# 2_cyber60-smk_matrix.net
KiCad netlist of a schematic drawn in Altium Designer
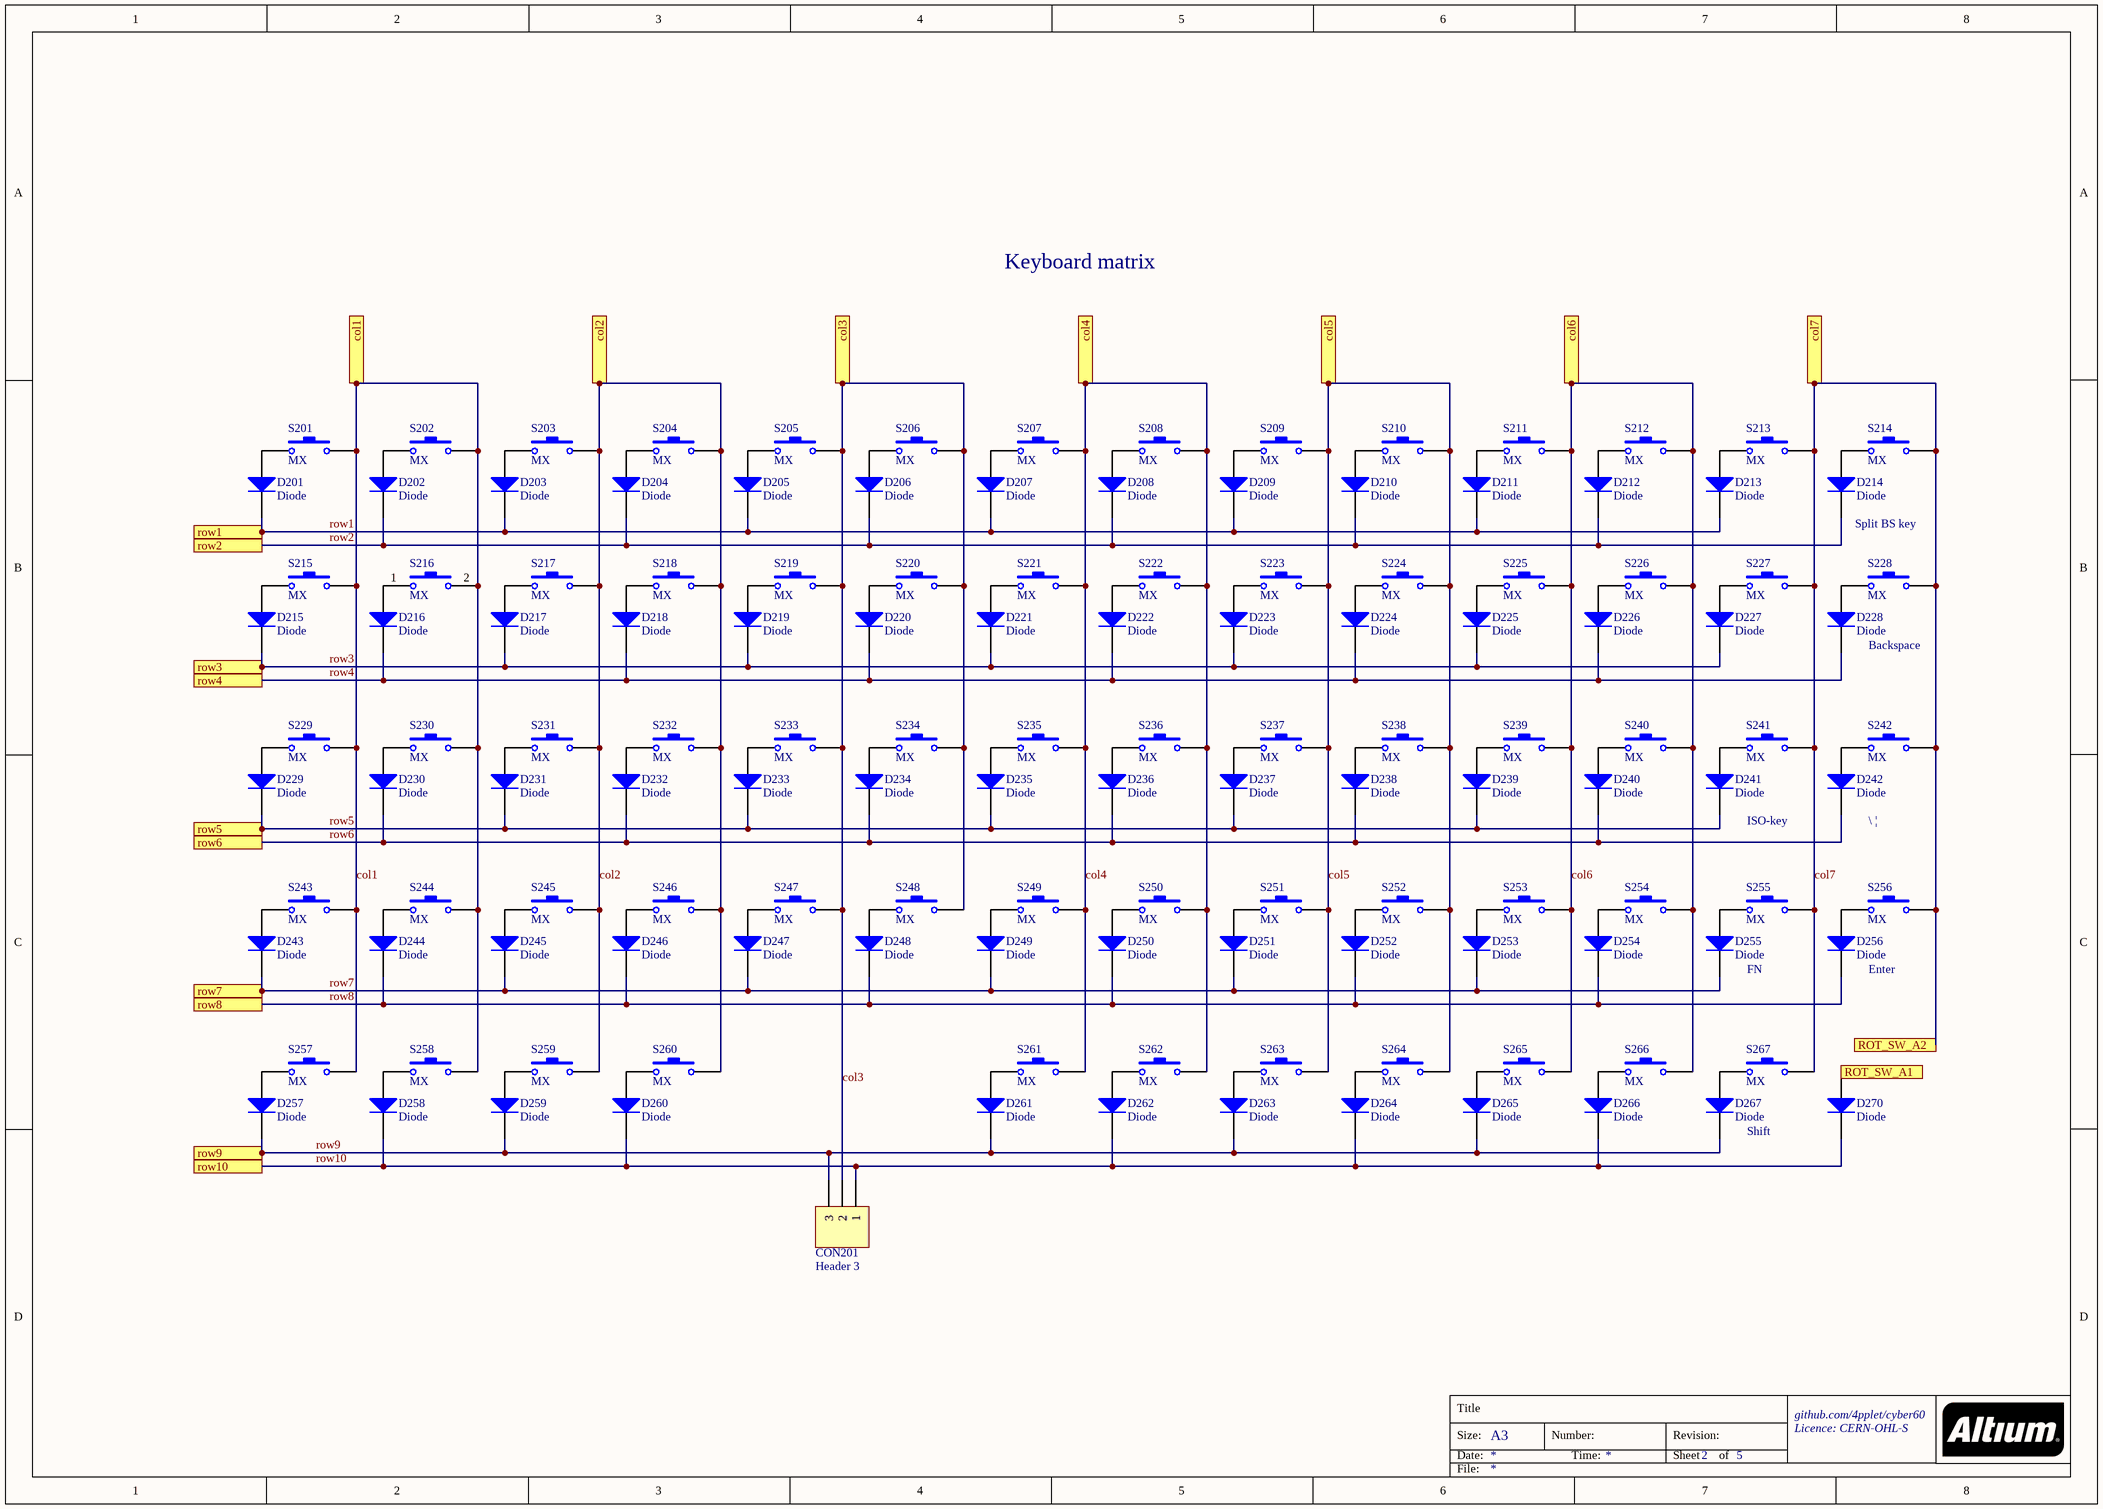
[diagram p0: 2_cyber60-smk_matrix.SchDoc]

(export (version "E")
  (design (tool "Eeschema 10.0.6"))
  (components
    (comp (ref "CON201")
      (value "Header 3")
      (footprint "HDR1X3")
      (description "Header, 3-Pin")
      (libsource (lib "Miscellaneous Connectors") (part "Header 3"))
    )
    (comp (ref "D201")
      (value "Diode")
      (footprint "SOD-123")
      (description "Default Diode")
      (fields (field (name "LCSC PART #") "C81598") (field (name "MRF.PART") "1N4148W"))
      (libsource (lib "Miscellaneous Devices") (part "Diode"))
    )
    (comp (ref "D202")
      (value "Diode")
      (footprint "SOD-123")
      (description "Default Diode")
      (fields (field (name "LCSC PART #") "C81598") (field (name "MRF.PART") "1N4148W"))
      (libsource (lib "Miscellaneous Devices") (part "Diode"))
    )
    (comp (ref "D203")
      (value "Diode")
      (footprint "SOD-123")
      (description "Default Diode")
      (fields (field (name "LCSC PART #") "C81598") (field (name "MRF.PART") "1N4148W"))
      (libsource (lib "Miscellaneous Devices") (part "Diode"))
    )
    (comp (ref "D204")
      (value "Diode")
      (footprint "SOD-123")
      (description "Default Diode")
      (fields (field (name "LCSC PART #") "C81598") (field (name "MRF.PART") "1N4148W"))
      (libsource (lib "Miscellaneous Devices") (part "Diode"))
    )
    (comp (ref "D205")
      (value "Diode")
      (footprint "SOD-123")
      (description "Default Diode")
      (fields (field (name "LCSC PART #") "C81598") (field (name "MRF.PART") "1N4148W"))
      (libsource (lib "Miscellaneous Devices") (part "Diode"))
    )
    (comp (ref "D206")
      (value "Diode")
      (footprint "SOD-123")
      (description "Default Diode")
      (fields (field (name "LCSC PART #") "C81598") (field (name "MRF.PART") "1N4148W"))
      (libsource (lib "Miscellaneous Devices") (part "Diode"))
    )
    (comp (ref "D207")
      (value "Diode")
      (footprint "SOD-123")
      (description "Default Diode")
      (fields (field (name "LCSC PART #") "C81598") (field (name "MRF.PART") "1N4148W"))
      (libsource (lib "Miscellaneous Devices") (part "Diode"))
    )
    (comp (ref "D208")
      (value "Diode")
      (footprint "SOD-123")
      (description "Default Diode")
      (fields (field (name "LCSC PART #") "C81598") (field (name "MRF.PART") "1N4148W"))
      (libsource (lib "Miscellaneous Devices") (part "Diode"))
    )
    (comp (ref "D209")
      (value "Diode")
      (footprint "SOD-123")
      (description "Default Diode")
      (fields (field (name "LCSC PART #") "C81598") (field (name "MRF.PART") "1N4148W"))
      (libsource (lib "Miscellaneous Devices") (part "Diode"))
    )
    (comp (ref "D210")
      (value "Diode")
      (footprint "SOD-123")
      (description "Default Diode")
      (fields (field (name "LCSC PART #") "C81598") (field (name "MRF.PART") "1N4148W"))
      (libsource (lib "Miscellaneous Devices") (part "Diode"))
    )
    (comp (ref "D211")
      (value "Diode")
      (footprint "SOD-123")
      (description "Default Diode")
      (fields (field (name "LCSC PART #") "C81598") (field (name "MRF.PART") "1N4148W"))
      (libsource (lib "Miscellaneous Devices") (part "Diode"))
    )
    (comp (ref "D212")
      (value "Diode")
      (footprint "SOD-123")
      (description "Default Diode")
      (fields (field (name "LCSC PART #") "C81598") (field (name "MRF.PART") "1N4148W"))
      (libsource (lib "Miscellaneous Devices") (part "Diode"))
    )
    (comp (ref "D213")
      (value "Diode")
      (footprint "SOD-123")
      (description "Default Diode")
      (fields (field (name "LCSC PART #") "C81598") (field (name "MRF.PART") "1N4148W"))
      (libsource (lib "Miscellaneous Devices") (part "Diode"))
    )
    (comp (ref "D214")
      (value "Diode")
      (footprint "SOD-123")
      (description "Default Diode")
      (fields (field (name "LCSC PART #") "C81598") (field (name "MRF.PART") "1N4148W"))
      (libsource (lib "Miscellaneous Devices") (part "Diode"))
    )
    (comp (ref "D215")
      (value "Diode")
      (footprint "SOD-123")
      (description "Default Diode")
      (fields (field (name "LCSC PART #") "C81598") (field (name "MRF.PART") "1N4148W"))
      (libsource (lib "Miscellaneous Devices") (part "Diode"))
    )
    (comp (ref "D216")
      (value "Diode")
      (footprint "SOD-123")
      (description "Default Diode")
      (fields (field (name "LCSC PART #") "C81598") (field (name "MRF.PART") "1N4148W"))
      (libsource (lib "Miscellaneous Devices") (part "Diode"))
    )
    (comp (ref "D217")
      (value "Diode")
      (footprint "SOD-123")
      (description "Default Diode")
      (fields (field (name "LCSC PART #") "C81598") (field (name "MRF.PART") "1N4148W"))
      (libsource (lib "Miscellaneous Devices") (part "Diode"))
    )
    (comp (ref "D218")
      (value "Diode")
      (footprint "SOD-123")
      (description "Default Diode")
      (fields (field (name "LCSC PART #") "C81598") (field (name "MRF.PART") "1N4148W"))
      (libsource (lib "Miscellaneous Devices") (part "Diode"))
    )
    (comp (ref "D219")
      (value "Diode")
      (footprint "SOD-123")
      (description "Default Diode")
      (fields (field (name "LCSC PART #") "C81598") (field (name "MRF.PART") "1N4148W"))
      (libsource (lib "Miscellaneous Devices") (part "Diode"))
    )
    (comp (ref "D220")
      (value "Diode")
      (footprint "SOD-123")
      (description "Default Diode")
      (fields (field (name "LCSC PART #") "C81598") (field (name "MRF.PART") "1N4148W"))
      (libsource (lib "Miscellaneous Devices") (part "Diode"))
    )
    (comp (ref "D221")
      (value "Diode")
      (footprint "SOD-123")
      (description "Default Diode")
      (fields (field (name "LCSC PART #") "C81598") (field (name "MRF.PART") "1N4148W"))
      (libsource (lib "Miscellaneous Devices") (part "Diode"))
    )
    (comp (ref "D222")
      (value "Diode")
      (footprint "SOD-123")
      (description "Default Diode")
      (fields (field (name "LCSC PART #") "C81598") (field (name "MRF.PART") "1N4148W"))
      (libsource (lib "Miscellaneous Devices") (part "Diode"))
    )
    (comp (ref "D223")
      (value "Diode")
      (footprint "SOD-123")
      (description "Default Diode")
      (fields (field (name "LCSC PART #") "C81598") (field (name "MRF.PART") "1N4148W"))
      (libsource (lib "Miscellaneous Devices") (part "Diode"))
    )
    (comp (ref "D224")
      (value "Diode")
      (footprint "SOD-123")
      (description "Default Diode")
      (fields (field (name "LCSC PART #") "C81598") (field (name "MRF.PART") "1N4148W"))
      (libsource (lib "Miscellaneous Devices") (part "Diode"))
    )
    (comp (ref "D225")
      (value "Diode")
      (footprint "SOD-123")
      (description "Default Diode")
      (fields (field (name "LCSC PART #") "C81598") (field (name "MRF.PART") "1N4148W"))
      (libsource (lib "Miscellaneous Devices") (part "Diode"))
    )
    (comp (ref "D226")
      (value "Diode")
      (footprint "SOD-123")
      (description "Default Diode")
      (fields (field (name "LCSC PART #") "C81598") (field (name "MRF.PART") "1N4148W"))
      (libsource (lib "Miscellaneous Devices") (part "Diode"))
    )
    (comp (ref "D227")
      (value "Diode")
      (footprint "SOD-123")
      (description "Default Diode")
      (fields (field (name "LCSC PART #") "C81598") (field (name "MRF.PART") "1N4148W"))
      (libsource (lib "Miscellaneous Devices") (part "Diode"))
    )
    (comp (ref "D228")
      (value "Diode")
      (footprint "SOD-123")
      (description "Default Diode")
      (fields (field (name "LCSC PART #") "C81598") (field (name "MRF.PART") "1N4148W"))
      (libsource (lib "Miscellaneous Devices") (part "Diode"))
    )
    (comp (ref "D229")
      (value "Diode")
      (footprint "SOD-123")
      (description "Default Diode")
      (fields (field (name "LCSC PART #") "C81598") (field (name "MRF.PART") "1N4148W"))
      (libsource (lib "Miscellaneous Devices") (part "Diode"))
    )
    (comp (ref "D230")
      (value "Diode")
      (footprint "SOD-123")
      (description "Default Diode")
      (fields (field (name "LCSC PART #") "C81598") (field (name "MRF.PART") "1N4148W"))
      (libsource (lib "Miscellaneous Devices") (part "Diode"))
    )
    (comp (ref "D231")
      (value "Diode")
      (footprint "SOD-123")
      (description "Default Diode")
      (fields (field (name "LCSC PART #") "C81598") (field (name "MRF.PART") "1N4148W"))
      (libsource (lib "Miscellaneous Devices") (part "Diode"))
    )
    (comp (ref "D232")
      (value "Diode")
      (footprint "SOD-123")
      (description "Default Diode")
      (fields (field (name "LCSC PART #") "C81598") (field (name "MRF.PART") "1N4148W"))
      (libsource (lib "Miscellaneous Devices") (part "Diode"))
    )
    (comp (ref "D233")
      (value "Diode")
      (footprint "SOD-123")
      (description "Default Diode")
      (fields (field (name "LCSC PART #") "C81598") (field (name "MRF.PART") "1N4148W"))
      (libsource (lib "Miscellaneous Devices") (part "Diode"))
    )
    (comp (ref "D234")
      (value "Diode")
      (footprint "SOD-123")
      (description "Default Diode")
      (fields (field (name "LCSC PART #") "C81598") (field (name "MRF.PART") "1N4148W"))
      (libsource (lib "Miscellaneous Devices") (part "Diode"))
    )
    (comp (ref "D235")
      (value "Diode")
      (footprint "SOD-123")
      (description "Default Diode")
      (fields (field (name "LCSC PART #") "C81598") (field (name "MRF.PART") "1N4148W"))
      (libsource (lib "Miscellaneous Devices") (part "Diode"))
    )
    (comp (ref "D236")
      (value "Diode")
      (footprint "SOD-123")
      (description "Default Diode")
      (fields (field (name "LCSC PART #") "C81598") (field (name "MRF.PART") "1N4148W"))
      (libsource (lib "Miscellaneous Devices") (part "Diode"))
    )
    (comp (ref "D237")
      (value "Diode")
      (footprint "SOD-123")
      (description "Default Diode")
      (fields (field (name "LCSC PART #") "C81598") (field (name "MRF.PART") "1N4148W"))
      (libsource (lib "Miscellaneous Devices") (part "Diode"))
    )
    (comp (ref "D238")
      (value "Diode")
      (footprint "SOD-123")
      (description "Default Diode")
      (fields (field (name "LCSC PART #") "C81598") (field (name "MRF.PART") "1N4148W"))
      (libsource (lib "Miscellaneous Devices") (part "Diode"))
    )
    (comp (ref "D239")
      (value "Diode")
      (footprint "SOD-123")
      (description "Default Diode")
      (fields (field (name "LCSC PART #") "C81598") (field (name "MRF.PART") "1N4148W"))
      (libsource (lib "Miscellaneous Devices") (part "Diode"))
    )
    (comp (ref "D240")
      (value "Diode")
      (footprint "SOD-123")
      (description "Default Diode")
      (fields (field (name "LCSC PART #") "C81598") (field (name "MRF.PART") "1N4148W"))
      (libsource (lib "Miscellaneous Devices") (part "Diode"))
    )
    (comp (ref "D241")
      (value "Diode")
      (footprint "SOD-123")
      (description "Default Diode")
      (fields (field (name "LCSC PART #") "C81598") (field (name "MRF.PART") "1N4148W"))
      (libsource (lib "Miscellaneous Devices") (part "Diode"))
    )
    (comp (ref "D242")
      (value "Diode")
      (footprint "SOD-123")
      (description "Default Diode")
      (fields (field (name "LCSC PART #") "C81598") (field (name "MRF.PART") "1N4148W"))
      (libsource (lib "Miscellaneous Devices") (part "Diode"))
    )
    (comp (ref "D243")
      (value "Diode")
      (footprint "SOD-123")
      (description "Default Diode")
      (fields (field (name "LCSC PART #") "C81598") (field (name "MRF.PART") "1N4148W"))
      (libsource (lib "Miscellaneous Devices") (part "Diode"))
    )
    (comp (ref "D244")
      (value "Diode")
      (footprint "SOD-123")
      (description "Default Diode")
      (fields (field (name "LCSC PART #") "C81598") (field (name "MRF.PART") "1N4148W"))
      (libsource (lib "Miscellaneous Devices") (part "Diode"))
    )
    (comp (ref "D245")
      (value "Diode")
      (footprint "SOD-123")
      (description "Default Diode")
      (fields (field (name "LCSC PART #") "C81598") (field (name "MRF.PART") "1N4148W"))
      (libsource (lib "Miscellaneous Devices") (part "Diode"))
    )
    (comp (ref "D246")
      (value "Diode")
      (footprint "SOD-123")
      (description "Default Diode")
      (fields (field (name "LCSC PART #") "C81598") (field (name "MRF.PART") "1N4148W"))
      (libsource (lib "Miscellaneous Devices") (part "Diode"))
    )
    (comp (ref "D247")
      (value "Diode")
      (footprint "SOD-123")
      (description "Default Diode")
      (fields (field (name "LCSC PART #") "C81598") (field (name "MRF.PART") "1N4148W"))
      (libsource (lib "Miscellaneous Devices") (part "Diode"))
    )
    (comp (ref "D248")
      (value "Diode")
      (footprint "SOD-123")
      (description "Default Diode")
      (fields (field (name "LCSC PART #") "C81598") (field (name "MRF.PART") "1N4148W"))
      (libsource (lib "Miscellaneous Devices") (part "Diode"))
    )
    (comp (ref "D249")
      (value "Diode")
      (footprint "SOD-123")
      (description "Default Diode")
      (fields (field (name "LCSC PART #") "C81598") (field (name "MRF.PART") "1N4148W"))
      (libsource (lib "Miscellaneous Devices") (part "Diode"))
    )
    (comp (ref "D250")
      (value "Diode")
      (footprint "SOD-123")
      (description "Default Diode")
      (fields (field (name "LCSC PART #") "C81598") (field (name "MRF.PART") "1N4148W"))
      (libsource (lib "Miscellaneous Devices") (part "Diode"))
    )
    (comp (ref "D251")
      (value "Diode")
      (footprint "SOD-123")
      (description "Default Diode")
      (fields (field (name "LCSC PART #") "C81598") (field (name "MRF.PART") "1N4148W"))
      (libsource (lib "Miscellaneous Devices") (part "Diode"))
    )
    (comp (ref "D252")
      (value "Diode")
      (footprint "SOD-123")
      (description "Default Diode")
      (fields (field (name "LCSC PART #") "C81598") (field (name "MRF.PART") "1N4148W"))
      (libsource (lib "Miscellaneous Devices") (part "Diode"))
    )
    (comp (ref "D253")
      (value "Diode")
      (footprint "SOD-123")
      (description "Default Diode")
      (fields (field (name "LCSC PART #") "C81598") (field (name "MRF.PART") "1N4148W"))
      (libsource (lib "Miscellaneous Devices") (part "Diode"))
    )
    (comp (ref "D254")
      (value "Diode")
      (footprint "SOD-123")
      (description "Default Diode")
      (fields (field (name "LCSC PART #") "C81598") (field (name "MRF.PART") "1N4148W"))
      (libsource (lib "Miscellaneous Devices") (part "Diode"))
    )
    (comp (ref "D255")
      (value "Diode")
      (footprint "SOD-123")
      (description "Default Diode")
      (fields (field (name "LCSC PART #") "C81598") (field (name "MRF.PART") "1N4148W"))
      (libsource (lib "Miscellaneous Devices") (part "Diode"))
    )
    (comp (ref "D256")
      (value "Diode")
      (footprint "SOD-123")
      (description "Default Diode")
      (fields (field (name "LCSC PART #") "C81598") (field (name "MRF.PART") "1N4148W"))
      (libsource (lib "Miscellaneous Devices") (part "Diode"))
    )
    (comp (ref "D257")
      (value "Diode")
      (footprint "SOD-123")
      (description "Default Diode")
      (fields (field (name "LCSC PART #") "C81598") (field (name "MRF.PART") "1N4148W"))
      (libsource (lib "Miscellaneous Devices") (part "Diode"))
    )
    (comp (ref "D258")
      (value "Diode")
      (footprint "SOD-123")
      (description "Default Diode")
      (fields (field (name "LCSC PART #") "C81598") (field (name "MRF.PART") "1N4148W"))
      (libsource (lib "Miscellaneous Devices") (part "Diode"))
    )
    (comp (ref "D259")
      (value "Diode")
      (footprint "SOD-123")
      (description "Default Diode")
      (fields (field (name "LCSC PART #") "C81598") (field (name "MRF.PART") "1N4148W"))
      (libsource (lib "Miscellaneous Devices") (part "Diode"))
    )
    (comp (ref "D260")
      (value "Diode")
      (footprint "SOD-123")
      (description "Default Diode")
      (fields (field (name "LCSC PART #") "C81598") (field (name "MRF.PART") "1N4148W"))
      (libsource (lib "Miscellaneous Devices") (part "Diode"))
    )
    (comp (ref "D261")
      (value "Diode")
      (footprint "SOD-123")
      (description "Default Diode")
      (fields (field (name "LCSC PART #") "C81598") (field (name "MRF.PART") "1N4148W"))
      (libsource (lib "Miscellaneous Devices") (part "Diode"))
    )
    (comp (ref "D262")
      (value "Diode")
      (footprint "SOD-123")
      (description "Default Diode")
      (fields (field (name "LCSC PART #") "C81598") (field (name "MRF.PART") "1N4148W"))
      (libsource (lib "Miscellaneous Devices") (part "Diode"))
    )
    (comp (ref "D263")
      (value "Diode")
      (footprint "SOD-123")
      (description "Default Diode")
      (fields (field (name "LCSC PART #") "C81598") (field (name "MRF.PART") "1N4148W"))
      (libsource (lib "Miscellaneous Devices") (part "Diode"))
    )
    (comp (ref "D264")
      (value "Diode")
      (footprint "SOD-123")
      (description "Default Diode")
      (fields (field (name "LCSC PART #") "C81598") (field (name "MRF.PART") "1N4148W"))
      (libsource (lib "Miscellaneous Devices") (part "Diode"))
    )
    (comp (ref "D265")
      (value "Diode")
      (footprint "SOD-123")
      (description "Default Diode")
      (fields (field (name "LCSC PART #") "C81598") (field (name "MRF.PART") "1N4148W"))
      (libsource (lib "Miscellaneous Devices") (part "Diode"))
    )
    (comp (ref "D266")
      (value "Diode")
      (footprint "SOD-123")
      (description "Default Diode")
      (fields (field (name "LCSC PART #") "C81598") (field (name "MRF.PART") "1N4148W"))
      (libsource (lib "Miscellaneous Devices") (part "Diode"))
    )
    (comp (ref "D267")
      (value "Diode")
      (footprint "SOD-123")
      (description "Default Diode")
      (fields (field (name "LCSC PART #") "C81598") (field (name "MRF.PART") "1N4148W"))
      (libsource (lib "Miscellaneous Devices") (part "Diode"))
    )
    (comp (ref "D270")
      (value "Diode")
      (footprint "SOD-123")
      (description "Default Diode")
      (fields (field (name "LCSC PART #") "C81598") (field (name "MRF.PART") "1N4148W"))
      (libsource (lib "Miscellaneous Devices") (part "Diode"))
    )
    (comp (ref "S201")
      (value "MX")
      (footprint "SMK-switch - switched polarity")
      (description "Switch")
      (libsource (lib "Miscellaneous Devices") (part "SW-PB"))
    )
    (comp (ref "S202")
      (value "MX")
      (footprint "SMK-switch - switched polarity")
      (description "Switch")
      (libsource (lib "Miscellaneous Devices") (part "SW-PB"))
    )
    (comp (ref "S203")
      (value "MX")
      (footprint "SMK-switch - switched polarity")
      (description "Switch")
      (libsource (lib "Miscellaneous Devices") (part "SW-PB"))
    )
    (comp (ref "S204")
      (value "MX")
      (footprint "SMK-switch")
      (description "Switch")
      (libsource (lib "Miscellaneous Devices") (part "SW-PB"))
    )
    (comp (ref "S205")
      (value "MX")
      (footprint "SMK-switch - switched polarity")
      (description "Switch")
      (libsource (lib "Miscellaneous Devices") (part "SW-PB"))
    )
    (comp (ref "S206")
      (value "MX")
      (footprint "SMK-switch - switched polarity")
      (description "Switch")
      (libsource (lib "Miscellaneous Devices") (part "SW-PB"))
    )
    (comp (ref "S207")
      (value "MX")
      (footprint "SMK-switch - switched polarity")
      (description "Switch")
      (libsource (lib "Miscellaneous Devices") (part "SW-PB"))
    )
    (comp (ref "S208")
      (value "MX")
      (footprint "SMK-switch - switched polarity")
      (description "Switch")
      (libsource (lib "Miscellaneous Devices") (part "SW-PB"))
    )
    (comp (ref "S209")
      (value "MX")
      (footprint "SMK-switch - switched polarity")
      (description "Switch")
      (libsource (lib "Miscellaneous Devices") (part "SW-PB"))
    )
    (comp (ref "S210")
      (value "MX")
      (footprint "SMK-switch - switched polarity")
      (description "Switch")
      (libsource (lib "Miscellaneous Devices") (part "SW-PB"))
    )
    (comp (ref "S211")
      (value "MX")
      (footprint "SMK-switch")
      (description "Switch")
      (libsource (lib "Miscellaneous Devices") (part "SW-PB"))
    )
    (comp (ref "S212")
      (value "MX")
      (footprint "SMK-switch - switched polarity")
      (description "Switch")
      (libsource (lib "Miscellaneous Devices") (part "SW-PB"))
    )
    (comp (ref "S213")
      (value "MX")
      (footprint "SMK-switch")
      (description "Switch")
      (libsource (lib "Miscellaneous Devices") (part "SW-PB"))
    )
    (comp (ref "S214")
      (value "MX")
      (footprint "SMK-switch")
      (description "Switch")
      (libsource (lib "Miscellaneous Devices") (part "SW-PB"))
    )
    (comp (ref "S215")
      (value "MX")
      (footprint "SMK-switch - 1.5U")
      (description "TAB")
      (libsource (lib "Miscellaneous Devices") (part "SW-PB"))
    )
    (comp (ref "S216")
      (value "MX")
      (footprint "SMK-switch - switched polarity")
      (description "Switch")
      (libsource (lib "") (part "SW-PB_1"))
    )
    (comp (ref "S217")
      (value "MX")
      (footprint "SMK-switch - switched polarity")
      (description "Switch")
      (libsource (lib "Miscellaneous Devices") (part "SW-PB"))
    )
    (comp (ref "S218")
      (value "MX")
      (footprint "SMK-switch - switched polarity")
      (description "Switch")
      (libsource (lib "Miscellaneous Devices") (part "SW-PB"))
    )
    (comp (ref "S219")
      (value "MX")
      (footprint "SMK-switch - switched polarity")
      (description "Switch")
      (libsource (lib "Miscellaneous Devices") (part "SW-PB"))
    )
    (comp (ref "S220")
      (value "MX")
      (footprint "SMK-switch")
      (description "Switch")
      (libsource (lib "Miscellaneous Devices") (part "SW-PB"))
    )
    (comp (ref "S221")
      (value "MX")
      (footprint "SMK-switch - switched polarity")
      (description "Switch")
      (libsource (lib "Miscellaneous Devices") (part "SW-PB"))
    )
    (comp (ref "S222")
      (value "MX")
      (footprint "SMK-switch - switched polarity")
      (description "Switch")
      (libsource (lib "Miscellaneous Devices") (part "SW-PB"))
    )
    (comp (ref "S223")
      (value "MX")
      (footprint "SMK-switch - switched polarity")
      (description "Switch")
      (libsource (lib "Miscellaneous Devices") (part "SW-PB"))
    )
    (comp (ref "S224")
      (value "MX")
      (footprint "SMK-switch - switched polarity")
      (description "Switch")
      (libsource (lib "Miscellaneous Devices") (part "SW-PB"))
    )
    (comp (ref "S225")
      (value "MX")
      (footprint "SMK-switch - switched polarity")
      (description "Switch")
      (libsource (lib "Miscellaneous Devices") (part "SW-PB"))
    )
    (comp (ref "S226")
      (value "MX")
      (footprint "SMK-switch")
      (description "Switch")
      (libsource (lib "Miscellaneous Devices") (part "SW-PB"))
    )
    (comp (ref "S227")
      (value "MX")
      (footprint "SMK-switch")
      (description "Switch")
      (libsource (lib "Miscellaneous Devices") (part "SW-PB"))
    )
    (comp (ref "S228")
      (value "MX")
      (footprint "SMK-switch - backspace")
      (description "Switch")
      (libsource (lib "Miscellaneous Devices") (part "SW-PB"))
    )
    (comp (ref "S229")
      (value "MX")
      (footprint "SMK-switch - CAPS")
      (description "Switch")
      (libsource (lib "Miscellaneous Devices") (part "SW-PB"))
    )
    (comp (ref "S230")
      (value "MX")
      (footprint "SMK-switch - switched polarity")
      (description "Switch")
      (libsource (lib "Miscellaneous Devices") (part "SW-PB"))
    )
    (comp (ref "S231")
      (value "MX")
      (footprint "SMK-switch - switched polarity")
      (description "Switch")
      (libsource (lib "Miscellaneous Devices") (part "SW-PB"))
    )
    (comp (ref "S232")
      (value "MX")
      (footprint "SMK-switch - switched polarity")
      (description "Switch")
      (libsource (lib "Miscellaneous Devices") (part "SW-PB"))
    )
    (comp (ref "S233")
      (value "MX")
      (footprint "SMK-switch - switched polarity")
      (description "Switch")
      (libsource (lib "Miscellaneous Devices") (part "SW-PB"))
    )
    (comp (ref "S234")
      (value "MX")
      (footprint "SMK-switch")
      (description "Switch")
      (libsource (lib "Miscellaneous Devices") (part "SW-PB"))
    )
    (comp (ref "S235")
      (value "MX")
      (footprint "SMK-switch - switched polarity")
      (description "Switch")
      (libsource (lib "Miscellaneous Devices") (part "SW-PB"))
    )
    (comp (ref "S236")
      (value "MX")
      (footprint "SMK-switch - switched polarity")
      (description "Switch")
      (libsource (lib "Miscellaneous Devices") (part "SW-PB"))
    )
    (comp (ref "S237")
      (value "MX")
      (footprint "SMK-switch - switched polarity")
      (description "Switch")
      (libsource (lib "Miscellaneous Devices") (part "SW-PB"))
    )
    (comp (ref "S238")
      (value "MX")
      (footprint "SMK-switch - switched polarity")
      (description "Switch")
      (libsource (lib "Miscellaneous Devices") (part "SW-PB"))
    )
    (comp (ref "S239")
      (value "MX")
      (footprint "SMK-switch")
      (description "Switch")
      (libsource (lib "Miscellaneous Devices") (part "SW-PB"))
    )
    (comp (ref "S240")
      (value "MX")
      (footprint "SMK-switch - switched polarity")
      (description "Switch")
      (libsource (lib "Miscellaneous Devices") (part "SW-PB"))
    )
    (comp (ref "S241")
      (value "MX")
      (footprint "SMK-switch")
      (description "Switch")
      (libsource (lib "Miscellaneous Devices") (part "SW-PB"))
    )
    (comp (ref "S242")
      (value "MX")
      (footprint "SMK-switch - 1.5U")
      (description "Switch")
      (libsource (lib "Miscellaneous Devices") (part "SW-PB"))
    )
    (comp (ref "S243")
      (value "MX")
      (footprint "SMK-switch - Left shift v2")
      (description "Switch")
      (libsource (lib "Miscellaneous Devices") (part "SW-PB"))
    )
    (comp (ref "S244")
      (value "MX")
      (footprint "SMK-switch - switched polarity")
      (description "Switch")
      (libsource (lib "Miscellaneous Devices") (part "SW-PB"))
    )
    (comp (ref "S245")
      (value "MX")
      (footprint "SMK-switch - switched polarity")
      (description "Switch")
      (libsource (lib "Miscellaneous Devices") (part "SW-PB"))
    )
    (comp (ref "S246")
      (value "MX")
      (footprint "SMK-switch - switched polarity")
      (description "Switch")
      (libsource (lib "Miscellaneous Devices") (part "SW-PB"))
    )
    (comp (ref "S247")
      (value "MX")
      (footprint "SMK-switch - switched polarity")
      (description "Switch")
      (libsource (lib "Miscellaneous Devices") (part "SW-PB"))
    )
    (comp (ref "S248")
      (value "MX")
      (footprint "SMK-switch")
      (description "Switch")
      (libsource (lib "Miscellaneous Devices") (part "SW-PB"))
    )
    (comp (ref "S249")
      (value "MX")
      (footprint "SMK-switch - switched polarity")
      (description "Switch")
      (libsource (lib "Miscellaneous Devices") (part "SW-PB"))
    )
    (comp (ref "S250")
      (value "MX")
      (footprint "SMK-switch - switched polarity")
      (description "Switch")
      (libsource (lib "Miscellaneous Devices") (part "SW-PB"))
    )
    (comp (ref "S251")
      (value "MX")
      (footprint "SMK-switch - switched polarity")
      (description "Switch")
      (libsource (lib "Miscellaneous Devices") (part "SW-PB"))
    )
    (comp (ref "S252")
      (value "MX")
      (footprint "SMK-switch - switched polarity")
      (description "Switch")
      (libsource (lib "Miscellaneous Devices") (part "SW-PB"))
    )
    (comp (ref "S253")
      (value "MX")
      (footprint "SMK-switch - switched polarity")
      (description "Switch")
      (libsource (lib "Miscellaneous Devices") (part "SW-PB"))
    )
    (comp (ref "S254")
      (value "MX")
      (footprint "SMK-switch - switched polarity")
      (description "Switch")
      (libsource (lib "Miscellaneous Devices") (part "SW-PB"))
    )
    (comp (ref "S255")
      (value "MX")
      (footprint "SMK-switch")
      (description "Switch")
      (libsource (lib "Miscellaneous Devices") (part "SW-PB"))
    )
    (comp (ref "S256")
      (value "MX")
      (footprint "SMK-switch - Enter")
      (description "Switch")
      (libsource (lib "Miscellaneous Devices") (part "SW-PB"))
    )
    (comp (ref "S257")
      (value "MX")
      (footprint "SMK-switch - 1.5u MOD-L")
      (description "Switch")
      (libsource (lib "Miscellaneous Devices") (part "SW-PB"))
    )
    (comp (ref "S258")
      (value "MX")
      (footprint "SMK-switch - L_WIN V2")
      (description "Switch")
      (libsource (lib "Miscellaneous Devices") (part "SW-PB"))
    )
    (comp (ref "S259")
      (value "MX")
      (footprint "SMK-switch - L_ALT V2")
      (description "Switch")
      (libsource (lib "Miscellaneous Devices") (part "SW-PB"))
    )
    (comp (ref "S260")
      (value "MX")
      (footprint "SMK-switch - L split space_V2")
      (description "Switch")
      (libsource (lib "Miscellaneous Devices") (part "SW-PB"))
    )
    (comp (ref "S261")
      (value "MX")
      (footprint "SMK-switch - Space_V3")
      (description "Switch")
      (libsource (lib "Miscellaneous Devices") (part "SW-PB"))
    )
    (comp (ref "S262")
      (value "MX")
      (footprint "SMK-switch - R split space_V2")
      (description "Switch")
      (libsource (lib "Miscellaneous Devices") (part "SW-PB"))
    )
    (comp (ref "S263")
      (value "MX")
      (footprint "SMK-switch - switched polarity")
      (description "Switch")
      (libsource (lib "Miscellaneous Devices") (part "SW-PB"))
    )
    (comp (ref "S264")
      (value "MX")
      (footprint "SMK-switch - R_ALT V2")
      (description "Switch")
      (libsource (lib "Miscellaneous Devices") (part "SW-PB"))
    )
    (comp (ref "S265")
      (value "MX")
      (footprint "SMK-switch - R_WIN V2")
      (description "Switch")
      (libsource (lib "Miscellaneous Devices") (part "SW-PB"))
    )
    (comp (ref "S266")
      (value "MX")
      (footprint "SMK-switch - 1.5u MOD-R")
      (description "Switch")
      (libsource (lib "Miscellaneous Devices") (part "SW-PB"))
    )
    (comp (ref "S267")
      (value "MX")
      (footprint "SMK-switch - right shift v2")
      (description "Switch")
      (libsource (lib "Miscellaneous Devices") (part "SW-PB"))
    )
  )
  (nets
    (net (code "1") (name "/ROT_SW_A1") (class "Default")
      (node (ref "D270") (pin "1") (pinfunction "A_1") (pintype "passive"))
    )
    (net (code "2") (name "/col1") (class "Default")
      (node (ref "S201") (pin "1") (pinfunction "1_1") (pintype "passive"))
      (node (ref "S202") (pin "2") (pinfunction "2_2") (pintype "passive"))
      (node (ref "S215") (pin "1") (pinfunction "1_1") (pintype "passive"))
      (node (ref "S216") (pin "2") (pinfunction "2_2") (pintype "passive"))
      (node (ref "S229") (pin "1") (pinfunction "1_1") (pintype "passive"))
      (node (ref "S230") (pin "2") (pinfunction "2_2") (pintype "passive"))
      (node (ref "S243") (pin "1") (pinfunction "1_1") (pintype "passive"))
      (node (ref "S244") (pin "2") (pinfunction "2_2") (pintype "passive"))
      (node (ref "S257") (pin "1") (pinfunction "1_1") (pintype "passive"))
      (node (ref "S258") (pin "2") (pinfunction "2_2") (pintype "passive"))
    )
    (net (code "3") (name "/col2") (class "Default")
      (node (ref "S203") (pin "2") (pinfunction "2_2") (pintype "passive"))
      (node (ref "S204") (pin "2") (pinfunction "2_2") (pintype "passive"))
      (node (ref "S217") (pin "2") (pinfunction "2_2") (pintype "passive"))
      (node (ref "S218") (pin "2") (pinfunction "2_2") (pintype "passive"))
      (node (ref "S231") (pin "2") (pinfunction "2_2") (pintype "passive"))
      (node (ref "S232") (pin "2") (pinfunction "2_2") (pintype "passive"))
      (node (ref "S245") (pin "2") (pinfunction "2_2") (pintype "passive"))
      (node (ref "S246") (pin "2") (pinfunction "2_2") (pintype "passive"))
      (node (ref "S259") (pin "2") (pinfunction "2_2") (pintype "passive"))
      (node (ref "S260") (pin "2") (pinfunction "2_2") (pintype "passive"))
    )
    (net (code "4") (name "/col3") (class "Default")
      (node (ref "CON201") (pin "2") (pinfunction "2_2") (pintype "passive"))
      (node (ref "S205") (pin "2") (pinfunction "2_2") (pintype "passive"))
      (node (ref "S206") (pin "2") (pinfunction "2_2") (pintype "passive"))
      (node (ref "S219") (pin "2") (pinfunction "2_2") (pintype "passive"))
      (node (ref "S220") (pin "2") (pinfunction "2_2") (pintype "passive"))
      (node (ref "S233") (pin "2") (pinfunction "2_2") (pintype "passive"))
      (node (ref "S234") (pin "2") (pinfunction "2_2") (pintype "passive"))
      (node (ref "S247") (pin "2") (pinfunction "2_2") (pintype "passive"))
      (node (ref "S248") (pin "2") (pinfunction "2_2") (pintype "passive"))
    )
    (net (code "5") (name "/col4") (class "Default")
      (node (ref "S207") (pin "2") (pinfunction "2_2") (pintype "passive"))
      (node (ref "S208") (pin "2") (pinfunction "2_2") (pintype "passive"))
      (node (ref "S221") (pin "2") (pinfunction "2_2") (pintype "passive"))
      (node (ref "S222") (pin "2") (pinfunction "2_2") (pintype "passive"))
      (node (ref "S235") (pin "2") (pinfunction "2_2") (pintype "passive"))
      (node (ref "S236") (pin "2") (pinfunction "2_2") (pintype "passive"))
      (node (ref "S249") (pin "2") (pinfunction "2_2") (pintype "passive"))
      (node (ref "S250") (pin "2") (pinfunction "2_2") (pintype "passive"))
      (node (ref "S261") (pin "1") (pinfunction "1_1") (pintype "passive"))
      (node (ref "S262") (pin "2") (pinfunction "2_2") (pintype "passive"))
    )
    (net (code "6") (name "/col5") (class "Default")
      (node (ref "S209") (pin "2") (pinfunction "2_2") (pintype "passive"))
      (node (ref "S210") (pin "2") (pinfunction "2_2") (pintype "passive"))
      (node (ref "S223") (pin "2") (pinfunction "2_2") (pintype "passive"))
      (node (ref "S224") (pin "2") (pinfunction "2_2") (pintype "passive"))
      (node (ref "S237") (pin "2") (pinfunction "2_2") (pintype "passive"))
      (node (ref "S238") (pin "2") (pinfunction "2_2") (pintype "passive"))
      (node (ref "S251") (pin "2") (pinfunction "2_2") (pintype "passive"))
      (node (ref "S252") (pin "2") (pinfunction "2_2") (pintype "passive"))
      (node (ref "S263") (pin "2") (pinfunction "2_2") (pintype "passive"))
      (node (ref "S264") (pin "2") (pinfunction "2_2") (pintype "passive"))
    )
    (net (code "7") (name "/col6") (class "Default")
      (node (ref "S211") (pin "2") (pinfunction "2_2") (pintype "passive"))
      (node (ref "S212") (pin "2") (pinfunction "2_2") (pintype "passive"))
      (node (ref "S225") (pin "2") (pinfunction "2_2") (pintype "passive"))
      (node (ref "S226") (pin "2") (pinfunction "2_2") (pintype "passive"))
      (node (ref "S239") (pin "2") (pinfunction "2_2") (pintype "passive"))
      (node (ref "S240") (pin "2") (pinfunction "2_2") (pintype "passive"))
      (node (ref "S253") (pin "2") (pinfunction "2_2") (pintype "passive"))
      (node (ref "S254") (pin "2") (pinfunction "2_2") (pintype "passive"))
      (node (ref "S265") (pin "2") (pinfunction "2_2") (pintype "passive"))
      (node (ref "S266") (pin "2") (pinfunction "2_2") (pintype "passive"))
    )
    (net (code "8") (name "/col7") (class "Default")
      (node (ref "S213") (pin "2") (pinfunction "2_2") (pintype "passive"))
      (node (ref "S214") (pin "2") (pinfunction "2_2") (pintype "passive"))
      (node (ref "S227") (pin "2") (pinfunction "2_2") (pintype "passive"))
      (node (ref "S228") (pin "1") (pinfunction "1_1") (pintype "passive"))
      (node (ref "S241") (pin "2") (pinfunction "2_2") (pintype "passive"))
      (node (ref "S242") (pin "2") (pinfunction "2_2") (pintype "passive"))
      (node (ref "S255") (pin "2") (pinfunction "2_2") (pintype "passive"))
      (node (ref "S256") (pin "1") (pinfunction "1_1") (pintype "passive"))
      (node (ref "S267") (pin "2") (pinfunction "2_2") (pintype "passive"))
    )
    (net (code "9") (name "/row1") (class "Default")
      (node (ref "D201") (pin "2") (pinfunction "K_2") (pintype "passive"))
      (node (ref "D203") (pin "2") (pinfunction "K_2") (pintype "passive"))
      (node (ref "D205") (pin "2") (pinfunction "K_2") (pintype "passive"))
      (node (ref "D207") (pin "2") (pinfunction "K_2") (pintype "passive"))
      (node (ref "D209") (pin "2") (pinfunction "K_2") (pintype "passive"))
      (node (ref "D211") (pin "2") (pinfunction "K_2") (pintype "passive"))
      (node (ref "D213") (pin "2") (pinfunction "K_2") (pintype "passive"))
    )
    (net (code "10") (name "/row2") (class "Default")
      (node (ref "D202") (pin "2") (pinfunction "K_2") (pintype "passive"))
      (node (ref "D204") (pin "2") (pinfunction "K_2") (pintype "passive"))
      (node (ref "D206") (pin "2") (pinfunction "K_2") (pintype "passive"))
      (node (ref "D208") (pin "2") (pinfunction "K_2") (pintype "passive"))
      (node (ref "D210") (pin "2") (pinfunction "K_2") (pintype "passive"))
      (node (ref "D212") (pin "2") (pinfunction "K_2") (pintype "passive"))
      (node (ref "D214") (pin "2") (pinfunction "K_2") (pintype "passive"))
    )
    (net (code "11") (name "/row3") (class "Default")
      (node (ref "D215") (pin "2") (pinfunction "K_2") (pintype "passive"))
      (node (ref "D217") (pin "2") (pinfunction "K_2") (pintype "passive"))
      (node (ref "D219") (pin "2") (pinfunction "K_2") (pintype "passive"))
      (node (ref "D221") (pin "2") (pinfunction "K_2") (pintype "passive"))
      (node (ref "D223") (pin "2") (pinfunction "K_2") (pintype "passive"))
      (node (ref "D225") (pin "2") (pinfunction "K_2") (pintype "passive"))
      (node (ref "D227") (pin "2") (pinfunction "K_2") (pintype "passive"))
    )
    (net (code "12") (name "/row4") (class "Default")
      (node (ref "D216") (pin "2") (pinfunction "K_2") (pintype "passive"))
      (node (ref "D218") (pin "2") (pinfunction "K_2") (pintype "passive"))
      (node (ref "D220") (pin "2") (pinfunction "K_2") (pintype "passive"))
      (node (ref "D222") (pin "2") (pinfunction "K_2") (pintype "passive"))
      (node (ref "D224") (pin "2") (pinfunction "K_2") (pintype "passive"))
      (node (ref "D226") (pin "2") (pinfunction "K_2") (pintype "passive"))
      (node (ref "D228") (pin "2") (pinfunction "K_2") (pintype "passive"))
    )
    (net (code "13") (name "/row5") (class "Default")
      (node (ref "D229") (pin "2") (pinfunction "K_2") (pintype "passive"))
      (node (ref "D231") (pin "2") (pinfunction "K_2") (pintype "passive"))
      (node (ref "D233") (pin "2") (pinfunction "K_2") (pintype "passive"))
      (node (ref "D235") (pin "2") (pinfunction "K_2") (pintype "passive"))
      (node (ref "D237") (pin "2") (pinfunction "K_2") (pintype "passive"))
      (node (ref "D239") (pin "2") (pinfunction "K_2") (pintype "passive"))
      (node (ref "D241") (pin "2") (pinfunction "K_2") (pintype "passive"))
    )
    (net (code "14") (name "/row6") (class "Default")
      (node (ref "D230") (pin "2") (pinfunction "K_2") (pintype "passive"))
      (node (ref "D232") (pin "2") (pinfunction "K_2") (pintype "passive"))
      (node (ref "D234") (pin "2") (pinfunction "K_2") (pintype "passive"))
      (node (ref "D236") (pin "2") (pinfunction "K_2") (pintype "passive"))
      (node (ref "D238") (pin "2") (pinfunction "K_2") (pintype "passive"))
      (node (ref "D240") (pin "2") (pinfunction "K_2") (pintype "passive"))
      (node (ref "D242") (pin "2") (pinfunction "K_2") (pintype "passive"))
    )
    (net (code "15") (name "/row7") (class "Default")
      (node (ref "D243") (pin "2") (pinfunction "K_2") (pintype "passive"))
      (node (ref "D245") (pin "2") (pinfunction "K_2") (pintype "passive"))
      (node (ref "D247") (pin "2") (pinfunction "K_2") (pintype "passive"))
      (node (ref "D249") (pin "2") (pinfunction "K_2") (pintype "passive"))
      (node (ref "D251") (pin "2") (pinfunction "K_2") (pintype "passive"))
      (node (ref "D253") (pin "2") (pinfunction "K_2") (pintype "passive"))
      (node (ref "D255") (pin "2") (pinfunction "K_2") (pintype "passive"))
    )
    (net (code "16") (name "/row8") (class "Default")
      (node (ref "D244") (pin "2") (pinfunction "K_2") (pintype "passive"))
      (node (ref "D246") (pin "2") (pinfunction "K_2") (pintype "passive"))
      (node (ref "D248") (pin "2") (pinfunction "K_2") (pintype "passive"))
      (node (ref "D250") (pin "2") (pinfunction "K_2") (pintype "passive"))
      (node (ref "D252") (pin "2") (pinfunction "K_2") (pintype "passive"))
      (node (ref "D254") (pin "2") (pinfunction "K_2") (pintype "passive"))
      (node (ref "D256") (pin "2") (pinfunction "K_2") (pintype "passive"))
    )
    (net (code "17") (name "/row9") (class "Default")
      (node (ref "CON201") (pin "3") (pinfunction "3_3") (pintype "passive"))
      (node (ref "D257") (pin "2") (pinfunction "K_2") (pintype "passive"))
      (node (ref "D259") (pin "2") (pinfunction "K_2") (pintype "passive"))
      (node (ref "D261") (pin "2") (pinfunction "K_2") (pintype "passive"))
      (node (ref "D263") (pin "2") (pinfunction "K_2") (pintype "passive"))
      (node (ref "D265") (pin "2") (pinfunction "K_2") (pintype "passive"))
      (node (ref "D267") (pin "2") (pinfunction "K_2") (pintype "passive"))
    )
    (net (code "18") (name "/row10") (class "Default")
      (node (ref "CON201") (pin "1") (pinfunction "1_1") (pintype "passive"))
      (node (ref "D258") (pin "2") (pinfunction "K_2") (pintype "passive"))
      (node (ref "D260") (pin "2") (pinfunction "K_2") (pintype "passive"))
      (node (ref "D262") (pin "2") (pinfunction "K_2") (pintype "passive"))
      (node (ref "D264") (pin "2") (pinfunction "K_2") (pintype "passive"))
      (node (ref "D266") (pin "2") (pinfunction "K_2") (pintype "passive"))
      (node (ref "D270") (pin "2") (pinfunction "K_2") (pintype "passive"))
    )
    (net (code "19") (name "Net-(D201-A)") (class "Default")
      (node (ref "D201") (pin "1") (pinfunction "A_1") (pintype "passive"))
      (node (ref "S201") (pin "2") (pinfunction "2_2") (pintype "passive"))
    )
    (net (code "20") (name "Net-(D202-A)") (class "Default")
      (node (ref "D202") (pin "1") (pinfunction "A_1") (pintype "passive"))
      (node (ref "S202") (pin "1") (pinfunction "1_1") (pintype "passive"))
    )
    (net (code "21") (name "Net-(D203-A)") (class "Default")
      (node (ref "D203") (pin "1") (pinfunction "A_1") (pintype "passive"))
      (node (ref "S203") (pin "1") (pinfunction "1_1") (pintype "passive"))
    )
    (net (code "22") (name "Net-(D204-A)") (class "Default")
      (node (ref "D204") (pin "1") (pinfunction "A_1") (pintype "passive"))
      (node (ref "S204") (pin "1") (pinfunction "1_1") (pintype "passive"))
    )
    (net (code "23") (name "Net-(D205-A)") (class "Default")
      (node (ref "D205") (pin "1") (pinfunction "A_1") (pintype "passive"))
      (node (ref "S205") (pin "1") (pinfunction "1_1") (pintype "passive"))
    )
    (net (code "24") (name "Net-(D206-A)") (class "Default")
      (node (ref "D206") (pin "1") (pinfunction "A_1") (pintype "passive"))
      (node (ref "S206") (pin "1") (pinfunction "1_1") (pintype "passive"))
    )
    (net (code "25") (name "Net-(D207-A)") (class "Default")
      (node (ref "D207") (pin "1") (pinfunction "A_1") (pintype "passive"))
      (node (ref "S207") (pin "1") (pinfunction "1_1") (pintype "passive"))
    )
    (net (code "26") (name "Net-(D208-A)") (class "Default")
      (node (ref "D208") (pin "1") (pinfunction "A_1") (pintype "passive"))
      (node (ref "S208") (pin "1") (pinfunction "1_1") (pintype "passive"))
    )
    (net (code "27") (name "Net-(D209-A)") (class "Default")
      (node (ref "D209") (pin "1") (pinfunction "A_1") (pintype "passive"))
      (node (ref "S209") (pin "1") (pinfunction "1_1") (pintype "passive"))
    )
    (net (code "28") (name "Net-(D210-A)") (class "Default")
      (node (ref "D210") (pin "1") (pinfunction "A_1") (pintype "passive"))
      (node (ref "S210") (pin "1") (pinfunction "1_1") (pintype "passive"))
    )
    (net (code "29") (name "Net-(D211-A)") (class "Default")
      (node (ref "D211") (pin "1") (pinfunction "A_1") (pintype "passive"))
      (node (ref "S211") (pin "1") (pinfunction "1_1") (pintype "passive"))
    )
    (net (code "30") (name "Net-(D212-A)") (class "Default")
      (node (ref "D212") (pin "1") (pinfunction "A_1") (pintype "passive"))
      (node (ref "S212") (pin "1") (pinfunction "1_1") (pintype "passive"))
    )
    (net (code "31") (name "Net-(D213-A)") (class "Default")
      (node (ref "D213") (pin "1") (pinfunction "A_1") (pintype "passive"))
      (node (ref "S213") (pin "1") (pinfunction "1_1") (pintype "passive"))
    )
    (net (code "32") (name "Net-(D214-A)") (class "Default")
      (node (ref "D214") (pin "1") (pinfunction "A_1") (pintype "passive"))
      (node (ref "S214") (pin "1") (pinfunction "1_1") (pintype "passive"))
    )
    (net (code "33") (name "Net-(D215-A)") (class "Default")
      (node (ref "D215") (pin "1") (pinfunction "A_1") (pintype "passive"))
      (node (ref "S215") (pin "2") (pinfunction "2_2") (pintype "passive"))
    )
    (net (code "34") (name "Net-(D216-A)") (class "Default")
      (node (ref "D216") (pin "1") (pinfunction "A_1") (pintype "passive"))
      (node (ref "S216") (pin "1") (pinfunction "1_1") (pintype "passive"))
    )
    (net (code "35") (name "Net-(D217-A)") (class "Default")
      (node (ref "D217") (pin "1") (pinfunction "A_1") (pintype "passive"))
      (node (ref "S217") (pin "1") (pinfunction "1_1") (pintype "passive"))
    )
    (net (code "36") (name "Net-(D218-A)") (class "Default")
      (node (ref "D218") (pin "1") (pinfunction "A_1") (pintype "passive"))
      (node (ref "S218") (pin "1") (pinfunction "1_1") (pintype "passive"))
    )
    (net (code "37") (name "Net-(D219-A)") (class "Default")
      (node (ref "D219") (pin "1") (pinfunction "A_1") (pintype "passive"))
      (node (ref "S219") (pin "1") (pinfunction "1_1") (pintype "passive"))
    )
    (net (code "38") (name "Net-(D220-A)") (class "Default")
      (node (ref "D220") (pin "1") (pinfunction "A_1") (pintype "passive"))
      (node (ref "S220") (pin "1") (pinfunction "1_1") (pintype "passive"))
    )
    (net (code "39") (name "Net-(D221-A)") (class "Default")
      (node (ref "D221") (pin "1") (pinfunction "A_1") (pintype "passive"))
      (node (ref "S221") (pin "1") (pinfunction "1_1") (pintype "passive"))
    )
    (net (code "40") (name "Net-(D222-A)") (class "Default")
      (node (ref "D222") (pin "1") (pinfunction "A_1") (pintype "passive"))
      (node (ref "S222") (pin "1") (pinfunction "1_1") (pintype "passive"))
    )
    (net (code "41") (name "Net-(D223-A)") (class "Default")
      (node (ref "D223") (pin "1") (pinfunction "A_1") (pintype "passive"))
      (node (ref "S223") (pin "1") (pinfunction "1_1") (pintype "passive"))
    )
    (net (code "42") (name "Net-(D224-A)") (class "Default")
      (node (ref "D224") (pin "1") (pinfunction "A_1") (pintype "passive"))
      (node (ref "S224") (pin "1") (pinfunction "1_1") (pintype "passive"))
    )
    (net (code "43") (name "Net-(D225-A)") (class "Default")
      (node (ref "D225") (pin "1") (pinfunction "A_1") (pintype "passive"))
      (node (ref "S225") (pin "1") (pinfunction "1_1") (pintype "passive"))
    )
    (net (code "44") (name "Net-(D226-A)") (class "Default")
      (node (ref "D226") (pin "1") (pinfunction "A_1") (pintype "passive"))
      (node (ref "S226") (pin "1") (pinfunction "1_1") (pintype "passive"))
    )
    (net (code "45") (name "Net-(D227-A)") (class "Default")
      (node (ref "D227") (pin "1") (pinfunction "A_1") (pintype "passive"))
      (node (ref "S227") (pin "1") (pinfunction "1_1") (pintype "passive"))
    )
    (net (code "46") (name "Net-(D228-A)") (class "Default")
      (node (ref "D228") (pin "1") (pinfunction "A_1") (pintype "passive"))
      (node (ref "S228") (pin "2") (pinfunction "2_2") (pintype "passive"))
    )
    (net (code "47") (name "Net-(D229-A)") (class "Default")
      (node (ref "D229") (pin "1") (pinfunction "A_1") (pintype "passive"))
      (node (ref "S229") (pin "2") (pinfunction "2_2") (pintype "passive"))
    )
    (net (code "48") (name "Net-(D230-A)") (class "Default")
      (node (ref "D230") (pin "1") (pinfunction "A_1") (pintype "passive"))
      (node (ref "S230") (pin "1") (pinfunction "1_1") (pintype "passive"))
    )
    (net (code "49") (name "Net-(D231-A)") (class "Default")
      (node (ref "D231") (pin "1") (pinfunction "A_1") (pintype "passive"))
      (node (ref "S231") (pin "1") (pinfunction "1_1") (pintype "passive"))
    )
    (net (code "50") (name "Net-(D232-A)") (class "Default")
      (node (ref "D232") (pin "1") (pinfunction "A_1") (pintype "passive"))
      (node (ref "S232") (pin "1") (pinfunction "1_1") (pintype "passive"))
    )
    (net (code "51") (name "Net-(D233-A)") (class "Default")
      (node (ref "D233") (pin "1") (pinfunction "A_1") (pintype "passive"))
      (node (ref "S233") (pin "1") (pinfunction "1_1") (pintype "passive"))
    )
    (net (code "52") (name "Net-(D234-A)") (class "Default")
      (node (ref "D234") (pin "1") (pinfunction "A_1") (pintype "passive"))
      (node (ref "S234") (pin "1") (pinfunction "1_1") (pintype "passive"))
    )
    (net (code "53") (name "Net-(D235-A)") (class "Default")
      (node (ref "D235") (pin "1") (pinfunction "A_1") (pintype "passive"))
      (node (ref "S235") (pin "1") (pinfunction "1_1") (pintype "passive"))
    )
    (net (code "54") (name "Net-(D236-A)") (class "Default")
      (node (ref "D236") (pin "1") (pinfunction "A_1") (pintype "passive"))
      (node (ref "S236") (pin "1") (pinfunction "1_1") (pintype "passive"))
    )
    (net (code "55") (name "Net-(D237-A)") (class "Default")
      (node (ref "D237") (pin "1") (pinfunction "A_1") (pintype "passive"))
      (node (ref "S237") (pin "1") (pinfunction "1_1") (pintype "passive"))
    )
    (net (code "56") (name "Net-(D238-A)") (class "Default")
      (node (ref "D238") (pin "1") (pinfunction "A_1") (pintype "passive"))
      (node (ref "S238") (pin "1") (pinfunction "1_1") (pintype "passive"))
    )
    (net (code "57") (name "Net-(D239-A)") (class "Default")
      (node (ref "D239") (pin "1") (pinfunction "A_1") (pintype "passive"))
      (node (ref "S239") (pin "1") (pinfunction "1_1") (pintype "passive"))
    )
    (net (code "58") (name "Net-(D240-A)") (class "Default")
      (node (ref "D240") (pin "1") (pinfunction "A_1") (pintype "passive"))
      (node (ref "S240") (pin "1") (pinfunction "1_1") (pintype "passive"))
    )
    (net (code "59") (name "Net-(D241-A)") (class "Default")
      (node (ref "D241") (pin "1") (pinfunction "A_1") (pintype "passive"))
      (node (ref "S241") (pin "1") (pinfunction "1_1") (pintype "passive"))
    )
    (net (code "60") (name "Net-(D242-A)") (class "Default")
      (node (ref "D242") (pin "1") (pinfunction "A_1") (pintype "passive"))
      (node (ref "S242") (pin "1") (pinfunction "1_1") (pintype "passive"))
    )
    (net (code "61") (name "Net-(D243-A)") (class "Default")
      (node (ref "D243") (pin "1") (pinfunction "A_1") (pintype "passive"))
      (node (ref "S243") (pin "2") (pinfunction "2_2") (pintype "passive"))
    )
    (net (code "62") (name "Net-(D244-A)") (class "Default")
      (node (ref "D244") (pin "1") (pinfunction "A_1") (pintype "passive"))
      (node (ref "S244") (pin "1") (pinfunction "1_1") (pintype "passive"))
    )
    (net (code "63") (name "Net-(D245-A)") (class "Default")
      (node (ref "D245") (pin "1") (pinfunction "A_1") (pintype "passive"))
      (node (ref "S245") (pin "1") (pinfunction "1_1") (pintype "passive"))
    )
    (net (code "64") (name "Net-(D246-A)") (class "Default")
      (node (ref "D246") (pin "1") (pinfunction "A_1") (pintype "passive"))
      (node (ref "S246") (pin "1") (pinfunction "1_1") (pintype "passive"))
    )
    (net (code "65") (name "Net-(D247-A)") (class "Default")
      (node (ref "D247") (pin "1") (pinfunction "A_1") (pintype "passive"))
      (node (ref "S247") (pin "1") (pinfunction "1_1") (pintype "passive"))
    )
    (net (code "66") (name "Net-(D248-A)") (class "Default")
      (node (ref "D248") (pin "1") (pinfunction "A_1") (pintype "passive"))
      (node (ref "S248") (pin "1") (pinfunction "1_1") (pintype "passive"))
    )
    (net (code "67") (name "Net-(D249-A)") (class "Default")
      (node (ref "D249") (pin "1") (pinfunction "A_1") (pintype "passive"))
      (node (ref "S249") (pin "1") (pinfunction "1_1") (pintype "passive"))
    )
    (net (code "68") (name "Net-(D250-A)") (class "Default")
      (node (ref "D250") (pin "1") (pinfunction "A_1") (pintype "passive"))
      (node (ref "S250") (pin "1") (pinfunction "1_1") (pintype "passive"))
    )
    (net (code "69") (name "Net-(D251-A)") (class "Default")
      (node (ref "D251") (pin "1") (pinfunction "A_1") (pintype "passive"))
      (node (ref "S251") (pin "1") (pinfunction "1_1") (pintype "passive"))
    )
    (net (code "70") (name "Net-(D252-A)") (class "Default")
      (node (ref "D252") (pin "1") (pinfunction "A_1") (pintype "passive"))
      (node (ref "S252") (pin "1") (pinfunction "1_1") (pintype "passive"))
    )
    (net (code "71") (name "Net-(D253-A)") (class "Default")
      (node (ref "D253") (pin "1") (pinfunction "A_1") (pintype "passive"))
      (node (ref "S253") (pin "1") (pinfunction "1_1") (pintype "passive"))
    )
    (net (code "72") (name "Net-(D254-A)") (class "Default")
      (node (ref "D254") (pin "1") (pinfunction "A_1") (pintype "passive"))
      (node (ref "S254") (pin "1") (pinfunction "1_1") (pintype "passive"))
    )
    (net (code "73") (name "Net-(D255-A)") (class "Default")
      (node (ref "D255") (pin "1") (pinfunction "A_1") (pintype "passive"))
      (node (ref "S255") (pin "1") (pinfunction "1_1") (pintype "passive"))
    )
    (net (code "74") (name "Net-(D256-A)") (class "Default")
      (node (ref "D256") (pin "1") (pinfunction "A_1") (pintype "passive"))
      (node (ref "S256") (pin "2") (pinfunction "2_2") (pintype "passive"))
    )
    (net (code "75") (name "Net-(D257-A)") (class "Default")
      (node (ref "D257") (pin "1") (pinfunction "A_1") (pintype "passive"))
      (node (ref "S257") (pin "2") (pinfunction "2_2") (pintype "passive"))
    )
    (net (code "76") (name "Net-(D258-A)") (class "Default")
      (node (ref "D258") (pin "1") (pinfunction "A_1") (pintype "passive"))
      (node (ref "S258") (pin "1") (pinfunction "1_1") (pintype "passive"))
    )
    (net (code "77") (name "Net-(D259-A)") (class "Default")
      (node (ref "D259") (pin "1") (pinfunction "A_1") (pintype "passive"))
      (node (ref "S259") (pin "1") (pinfunction "1_1") (pintype "passive"))
    )
    (net (code "78") (name "Net-(D260-A)") (class "Default")
      (node (ref "D260") (pin "1") (pinfunction "A_1") (pintype "passive"))
      (node (ref "S260") (pin "1") (pinfunction "1_1") (pintype "passive"))
    )
    (net (code "79") (name "Net-(D261-A)") (class "Default")
      (node (ref "D261") (pin "1") (pinfunction "A_1") (pintype "passive"))
      (node (ref "S261") (pin "2") (pinfunction "2_2") (pintype "passive"))
    )
    (net (code "80") (name "Net-(D262-A)") (class "Default")
      (node (ref "D262") (pin "1") (pinfunction "A_1") (pintype "passive"))
      (node (ref "S262") (pin "1") (pinfunction "1_1") (pintype "passive"))
    )
    (net (code "81") (name "Net-(D263-A)") (class "Default")
      (node (ref "D263") (pin "1") (pinfunction "A_1") (pintype "passive"))
      (node (ref "S263") (pin "1") (pinfunction "1_1") (pintype "passive"))
    )
    (net (code "82") (name "Net-(D264-A)") (class "Default")
      (node (ref "D264") (pin "1") (pinfunction "A_1") (pintype "passive"))
      (node (ref "S264") (pin "1") (pinfunction "1_1") (pintype "passive"))
    )
    (net (code "83") (name "Net-(D265-A)") (class "Default")
      (node (ref "D265") (pin "1") (pinfunction "A_1") (pintype "passive"))
      (node (ref "S265") (pin "1") (pinfunction "1_1") (pintype "passive"))
    )
    (net (code "84") (name "Net-(D266-A)") (class "Default")
      (node (ref "D266") (pin "1") (pinfunction "A_1") (pintype "passive"))
      (node (ref "S266") (pin "1") (pinfunction "1_1") (pintype "passive"))
    )
    (net (code "85") (name "Net-(D267-A)") (class "Default")
      (node (ref "D267") (pin "1") (pinfunction "A_1") (pintype "passive"))
      (node (ref "S267") (pin "1") (pinfunction "1_1") (pintype "passive"))
    )
  )
)
